# EntradasAnalogicas.net
KiCad netlist of a schematic drawn in Altium Designer
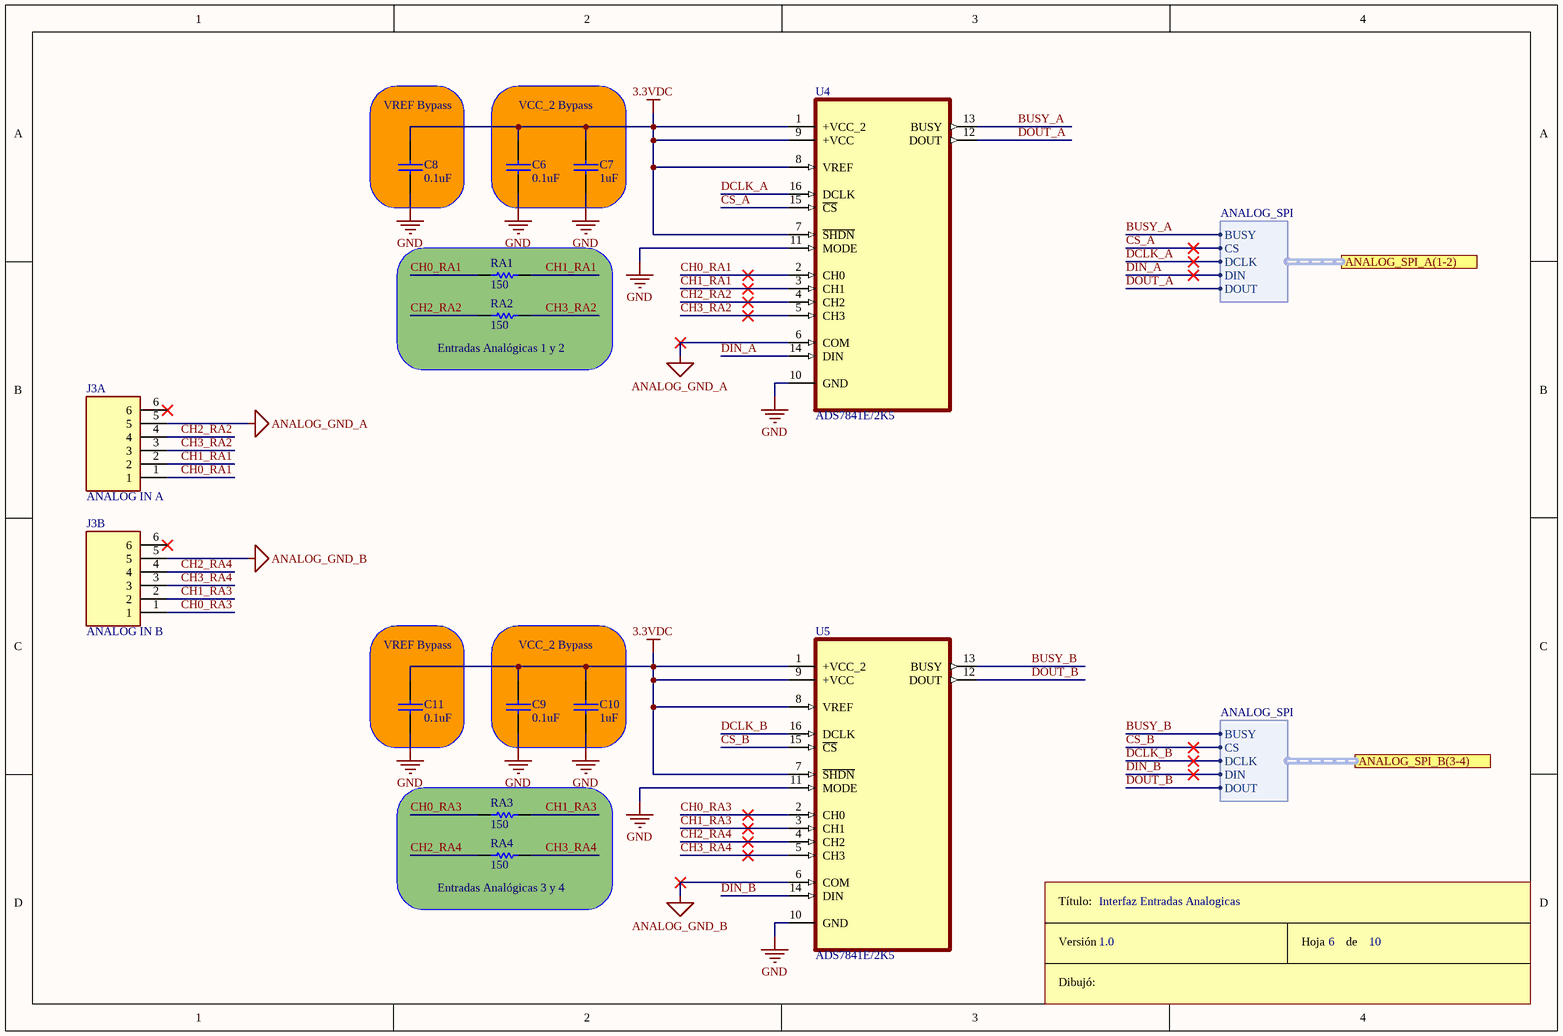
[diagram p0: EntradasAnalogicas.SchDoc]

(export (version "E")
  (design (tool "Eeschema 10.0.6"))
  (components
    (comp (ref "C6") (value "0.1uF") (footprint "CAP100") (libsource (lib "LIBEBAL") (part "CAP")))
    (comp (ref "C7") (value "1uF") (footprint "CAP200") (libsource (lib "LIBEBAL") (part "CAP")))
    (comp (ref "C8") (value "0.1uF") (footprint "CAP100") (libsource (lib "LIBEBAL") (part "CAP")))
    (comp (ref "C9") (value "0.1uF") (footprint "CAP100") (libsource (lib "LIBEBAL") (part "CAP")))
    (comp (ref "C10") (value "1uF") (footprint "CAP200") (libsource (lib "LIBEBAL") (part "CAP")))
    (comp (ref "C11") (value "0.1uF") (footprint "CAP100") (libsource (lib "LIBEBAL") (part "CAP")))
    (comp (ref "J3A")
      (value "ANALOG IN A")
      (footprint "TE_1586863-6")
      (description "Conn Power HDR 6 POS 4.2mm Solder RA Thru-Hole 6 Terminal 1 Port Tray")
      (fields (field (name "MF") "TE Connectivity") (field (name "MP") "1586863-6"))
      (libsource (lib "MFW6R") (part "1586863-6"))
    )
    (comp (ref "J3B")
      (value "ANALOG IN B")
      (footprint "TE_1586863-6")
      (description "Conn Power HDR 6 POS 4.2mm Solder RA Thru-Hole 6 Terminal 1 Port Tray")
      (fields (field (name "MF") "TE Connectivity") (field (name "MP") "1586863-6"))
      (libsource (lib "MFW6R") (part "1586863-6"))
    )
    (comp (ref "RA1") (value "150") (footprint "RES400") (libsource (lib "LIBEBAL") (part "RES")))
    (comp (ref "RA2") (value "150") (footprint "RES400") (libsource (lib "LIBEBAL") (part "RES")))
    (comp (ref "RA3") (value "150") (footprint "RES400") (libsource (lib "LIBEBAL") (part "RES")))
    (comp (ref "RA4") (value "150") (footprint "RES400") (libsource (lib "LIBEBAL") (part "RES")))
    (comp (ref "ROT4") (value "Rótulo") (libsource (lib "LIB PIO IX") (part "Rótulo")))
    (comp (ref "U4")
      (value "ADS7841E/2K5")
      (footprint "SOP63P600X175-16N")
      (description "ANALOG-TO-DIGITAL CONVERTER")
      (libsource (lib "ADS7841E_2K5") (part "ADS7841E/2K5"))
    )
    (comp (ref "U5")
      (value "ADS7841E/2K5")
      (footprint "SOP63P600X175-16N")
      (description "ANALOG-TO-DIGITAL CONVERTER")
      (libsource (lib "ADS7841E_2K5") (part "ADS7841E/2K5"))
    )
  )
  (nets
    (net (code "2") (name "/BUSY_A") (class "Default")
      (node (ref "U4") (pin "13") (pinfunction "BUSY_13") (pintype "output"))
    )
    (net (code "3") (name "/BUSY_B") (class "Default")
      (node (ref "U5") (pin "13") (pinfunction "BUSY_13") (pintype "output"))
    )
    (net (code "4") (name "/CH0_RA1") (class "Default")
      (node (ref "J3A") (pin "1") (pinfunction "1_1") (pintype "passive"))
      (node (ref "RA1") (pin "1") (pinfunction "1_1") (pintype "passive"))
      (node (ref "U4") (pin "2") (pinfunction "CH0_2") (pintype "input"))
    )
    (net (code "5") (name "/CH0_RA3") (class "Default")
      (node (ref "J3B") (pin "1") (pinfunction "1_1") (pintype "passive"))
      (node (ref "RA3") (pin "1") (pinfunction "1_1") (pintype "passive"))
      (node (ref "U5") (pin "2") (pinfunction "CH0_2") (pintype "input"))
    )
    (net (code "6") (name "/CH1_RA1") (class "Default")
      (node (ref "J3A") (pin "2") (pinfunction "2_2") (pintype "passive"))
      (node (ref "RA1") (pin "2") (pinfunction "2_2") (pintype "passive"))
      (node (ref "U4") (pin "3") (pinfunction "CH1_3") (pintype "input"))
    )
    (net (code "7") (name "/CH1_RA3") (class "Default")
      (node (ref "J3B") (pin "2") (pinfunction "2_2") (pintype "passive"))
      (node (ref "RA3") (pin "2") (pinfunction "2_2") (pintype "passive"))
      (node (ref "U5") (pin "3") (pinfunction "CH1_3") (pintype "input"))
    )
    (net (code "8") (name "/CH2_RA2") (class "Default")
      (node (ref "J3A") (pin "4") (pinfunction "4_4") (pintype "passive"))
      (node (ref "RA2") (pin "1") (pinfunction "1_1") (pintype "passive"))
      (node (ref "U4") (pin "4") (pinfunction "CH2_4") (pintype "input"))
    )
    (net (code "9") (name "/CH2_RA4") (class "Default")
      (node (ref "J3B") (pin "4") (pinfunction "4_4") (pintype "passive"))
      (node (ref "RA4") (pin "1") (pinfunction "1_1") (pintype "passive"))
      (node (ref "U5") (pin "4") (pinfunction "CH2_4") (pintype "input"))
    )
    (net (code "10") (name "/CH3_RA2") (class "Default")
      (node (ref "J3A") (pin "3") (pinfunction "3_3") (pintype "passive"))
      (node (ref "RA2") (pin "2") (pinfunction "2_2") (pintype "passive"))
      (node (ref "U4") (pin "5") (pinfunction "CH3_5") (pintype "input"))
    )
    (net (code "11") (name "/CH3_RA4") (class "Default")
      (node (ref "J3B") (pin "3") (pinfunction "3_3") (pintype "passive"))
      (node (ref "RA4") (pin "2") (pinfunction "2_2") (pintype "passive"))
      (node (ref "U5") (pin "5") (pinfunction "CH3_5") (pintype "input"))
    )
    (net (code "12") (name "/CS_A") (class "Default")
      (node (ref "U4") (pin "15") (pinfunction "~{CS}_15") (pintype "input"))
    )
    (net (code "13") (name "/CS_B") (class "Default")
      (node (ref "U5") (pin "15") (pinfunction "~{CS}_15") (pintype "input"))
    )
    (net (code "14") (name "/DCLK_A") (class "Default")
      (node (ref "U4") (pin "16") (pinfunction "DCLK_16") (pintype "input"))
    )
    (net (code "15") (name "/DCLK_B") (class "Default")
      (node (ref "U5") (pin "16") (pinfunction "DCLK_16") (pintype "input"))
    )
    (net (code "16") (name "/DIN_A") (class "Default")
      (node (ref "U4") (pin "14") (pinfunction "DIN_14") (pintype "input"))
    )
    (net (code "17") (name "/DIN_B") (class "Default")
      (node (ref "U5") (pin "14") (pinfunction "DIN_14") (pintype "input"))
    )
    (net (code "18") (name "/DOUT_A") (class "Default")
      (node (ref "U4") (pin "12") (pinfunction "DOUT_12") (pintype "output"))
    )
    (net (code "19") (name "/DOUT_B") (class "Default")
      (node (ref "U5") (pin "12") (pinfunction "DOUT_12") (pintype "output"))
    )
    (net (code "21") (name "3.3VDC") (class "Default")
      (node (ref "C10") (pin "1") (pinfunction "1_1") (pintype "passive"))
      (node (ref "C11") (pin "1") (pinfunction "1_1") (pintype "passive"))
      (node (ref "C6") (pin "1") (pinfunction "1_1") (pintype "passive"))
      (node (ref "C7") (pin "1") (pinfunction "1_1") (pintype "passive"))
      (node (ref "C8") (pin "1") (pinfunction "1_1") (pintype "passive"))
      (node (ref "C9") (pin "1") (pinfunction "1_1") (pintype "passive"))
      (node (ref "U4") (pin "1") (pinfunction "+VCC_2_1") (pintype "power_in"))
      (node (ref "U4") (pin "7") (pinfunction "~{SHDN}_7") (pintype "input"))
      (node (ref "U4") (pin "8") (pinfunction "VREF_8") (pintype "input"))
      (node (ref "U4") (pin "9") (pinfunction "+VCC_9") (pintype "power_in"))
      (node (ref "U5") (pin "1") (pinfunction "+VCC_2_1") (pintype "power_in"))
      (node (ref "U5") (pin "7") (pinfunction "~{SHDN}_7") (pintype "input"))
      (node (ref "U5") (pin "8") (pinfunction "VREF_8") (pintype "input"))
      (node (ref "U5") (pin "9") (pinfunction "+VCC_9") (pintype "power_in"))
    )
    (net (code "22") (name "ANALOG_GND_A") (class "Default")
      (node (ref "J3A") (pin "5") (pinfunction "5_5") (pintype "passive"))
      (node (ref "U4") (pin "6") (pinfunction "COM_6") (pintype "input"))
    )
    (net (code "23") (name "ANALOG_GND_B") (class "Default")
      (node (ref "J3B") (pin "5") (pinfunction "5_5") (pintype "passive"))
      (node (ref "U5") (pin "6") (pinfunction "COM_6") (pintype "input"))
    )
    (net (code "24") (name "GND") (class "Default")
      (node (ref "C10") (pin "2") (pinfunction "2_2") (pintype "passive"))
      (node (ref "C11") (pin "2") (pinfunction "2_2") (pintype "passive"))
      (node (ref "C6") (pin "2") (pinfunction "2_2") (pintype "passive"))
      (node (ref "C7") (pin "2") (pinfunction "2_2") (pintype "passive"))
      (node (ref "C8") (pin "2") (pinfunction "2_2") (pintype "passive"))
      (node (ref "C9") (pin "2") (pinfunction "2_2") (pintype "passive"))
      (node (ref "U4") (pin "10") (pinfunction "GND_10") (pintype "passive"))
      (node (ref "U4") (pin "11") (pinfunction "MODE_11") (pintype "input"))
      (node (ref "U5") (pin "10") (pinfunction "GND_10") (pintype "passive"))
      (node (ref "U5") (pin "11") (pinfunction "MODE_11") (pintype "input"))
    )
    (net (code "25") (name "unconnected-(J3A-Pad6)") (class "Default")
      (node (ref "J3A") (pin "6") (pinfunction "6_6") (pintype "passive+no_connect"))
    )
    (net (code "26") (name "unconnected-(J3B-Pad6)") (class "Default")
      (node (ref "J3B") (pin "6") (pinfunction "6_6") (pintype "passive+no_connect"))
    )
  )
)
